# Aex.net
KiCad netlist of a schematic drawn in Altium Designer
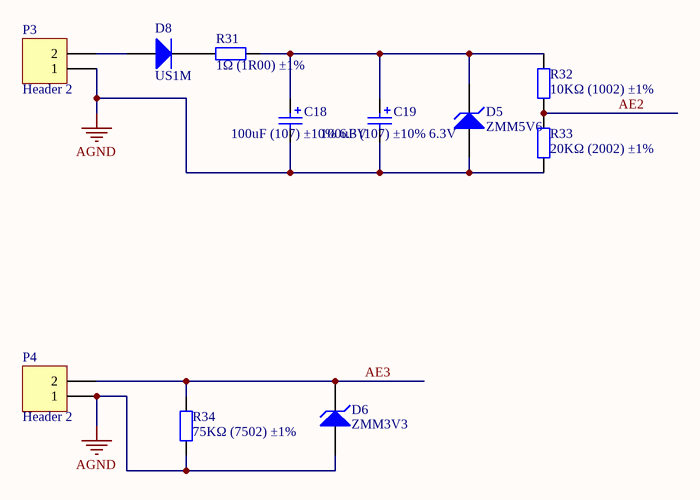
[diagram p0: Aex.SchDoc]

(export (version "E")
  (design (tool "Eeschema 10.0.6"))
  (components
    (comp (ref "C18")
      (value "100uF (107) ±10% 6.3V")
      (footprint "CASE-B_3528")
      (description "钽电容")
      (libsource (lib "Miscellaneous Devices LC") (part "3528 100uF (107) 10% 6.3V"))
    )
    (comp (ref "C19")
      (value "100uF (107) ±10% 6.3V")
      (footprint "CASE-B_3528")
      (description "钽电容")
      (libsource (lib "Miscellaneous Devices LC") (part "3528 100uF (107) 10% 6.3V"))
    )
    (comp (ref "D5")
      (value "ZMM5V6")
      (footprint "LL-34")
      (description "稳压二极管")
      (libsource (lib "Miscellaneous Devices LC") (part "LL-34 ZMM5V6"))
    )
    (comp (ref "D6")
      (value "ZMM3V3")
      (footprint "LL-34")
      (description "稳压二极管")
      (libsource (lib "Miscellaneous Devices LC") (part "LL-34 ZMM3V3"))
    )
    (comp (ref "D8")
      (value "US1M")
      (footprint "SMA(DO-214AC)_S1")
      (description "二极管")
      (libsource (lib "Miscellaneous Devices LC") (part "SMA(DO-214AC) US1M"))
    )
    (comp (ref "P3")
      (value "Header 2")
      (footprint "HDR1X2")
      (description "Header, 2-Pin")
      (fields (field (name "PUBLISHER") "Altium Limited"))
      (libsource (lib "Miscellaneous Connectors") (part "Header 2"))
    )
    (comp (ref "P4")
      (value "Header 2")
      (footprint "HDR1X2")
      (description "Header, 2-Pin")
      (fields (field (name "PUBLISHER") "Altium Limited"))
      (libsource (lib "Miscellaneous Connectors") (part "Header 2"))
    )
    (comp (ref "R31")
      (value "1Ω (1R00) ±1%")
      (footprint "0603_R")
      (description "贴片电阻")
      (libsource (lib "Miscellaneous Devices LC") (part "0603 1Ω (1R00) 1%"))
    )
    (comp (ref "R32")
      (value "10KΩ (1002) ±1%")
      (footprint "0603_R")
      (description "贴片电阻")
      (libsource (lib "Miscellaneous Devices LC") (part "0603 10KΩ (1002) 1%"))
    )
    (comp (ref "R33")
      (value "20KΩ (2002) ±1%")
      (footprint "0603_R")
      (description "贴片电阻")
      (libsource (lib "Miscellaneous Devices LC") (part "0603 20KΩ (2002) 1%"))
    )
    (comp (ref "R34")
      (value "75KΩ (7502) ±1%")
      (footprint "0603_R")
      (description "贴片电阻")
      (libsource (lib "Miscellaneous Devices LC") (part "0603 75KΩ (7502) 1%"))
    )
  )
  (nets
    (net (code "1") (name "/AE2") (class "Default")
      (node (ref "R32") (pin "1") (pinfunction "1_1") (pintype "passive"))
      (node (ref "R33") (pin "2") (pinfunction "2_2") (pintype "passive"))
    )
    (net (code "2") (name "/AE3") (class "Default")
      (node (ref "D6") (pin "2") (pinfunction "K_2") (pintype "passive"))
      (node (ref "P4") (pin "2") (pinfunction "2_2") (pintype "passive"))
      (node (ref "R34") (pin "2") (pinfunction "2_2") (pintype "passive"))
    )
    (net (code "3") (name "AGND") (class "Default")
      (node (ref "C18") (pin "2") (pinfunction "2_2") (pintype "passive"))
      (node (ref "C19") (pin "2") (pinfunction "2_2") (pintype "passive"))
      (node (ref "D5") (pin "1") (pinfunction "A_1") (pintype "passive"))
      (node (ref "D6") (pin "1") (pinfunction "A_1") (pintype "passive"))
      (node (ref "P3") (pin "1") (pinfunction "1_1") (pintype "passive"))
      (node (ref "P4") (pin "1") (pinfunction "1_1") (pintype "passive"))
      (node (ref "R33") (pin "1") (pinfunction "1_1") (pintype "passive"))
      (node (ref "R34") (pin "1") (pinfunction "1_1") (pintype "passive"))
    )
    (net (code "4") (name "Net-(D5-K)") (class "Default")
      (node (ref "C18") (pin "1") (pinfunction "1_1") (pintype "passive"))
      (node (ref "C19") (pin "1") (pinfunction "1_1") (pintype "passive"))
      (node (ref "D5") (pin "2") (pinfunction "K_2") (pintype "passive"))
      (node (ref "R31") (pin "2") (pinfunction "2_2") (pintype "passive"))
      (node (ref "R32") (pin "2") (pinfunction "2_2") (pintype "passive"))
    )
    (net (code "5") (name "Net-(D8-A)") (class "Default")
      (node (ref "D8") (pin "1") (pinfunction "A_1") (pintype "passive"))
      (node (ref "P3") (pin "2") (pinfunction "2_2") (pintype "passive"))
    )
    (net (code "6") (name "Net-(D8-K)") (class "Default")
      (node (ref "D8") (pin "2") (pinfunction "K_2") (pintype "passive"))
      (node (ref "R31") (pin "1") (pinfunction "1_1") (pintype "passive"))
    )
  )
)
